# SparkFun_u-blox_SAM-M10Q.net
KiCad netlist of a schematic drawn in EAGLE
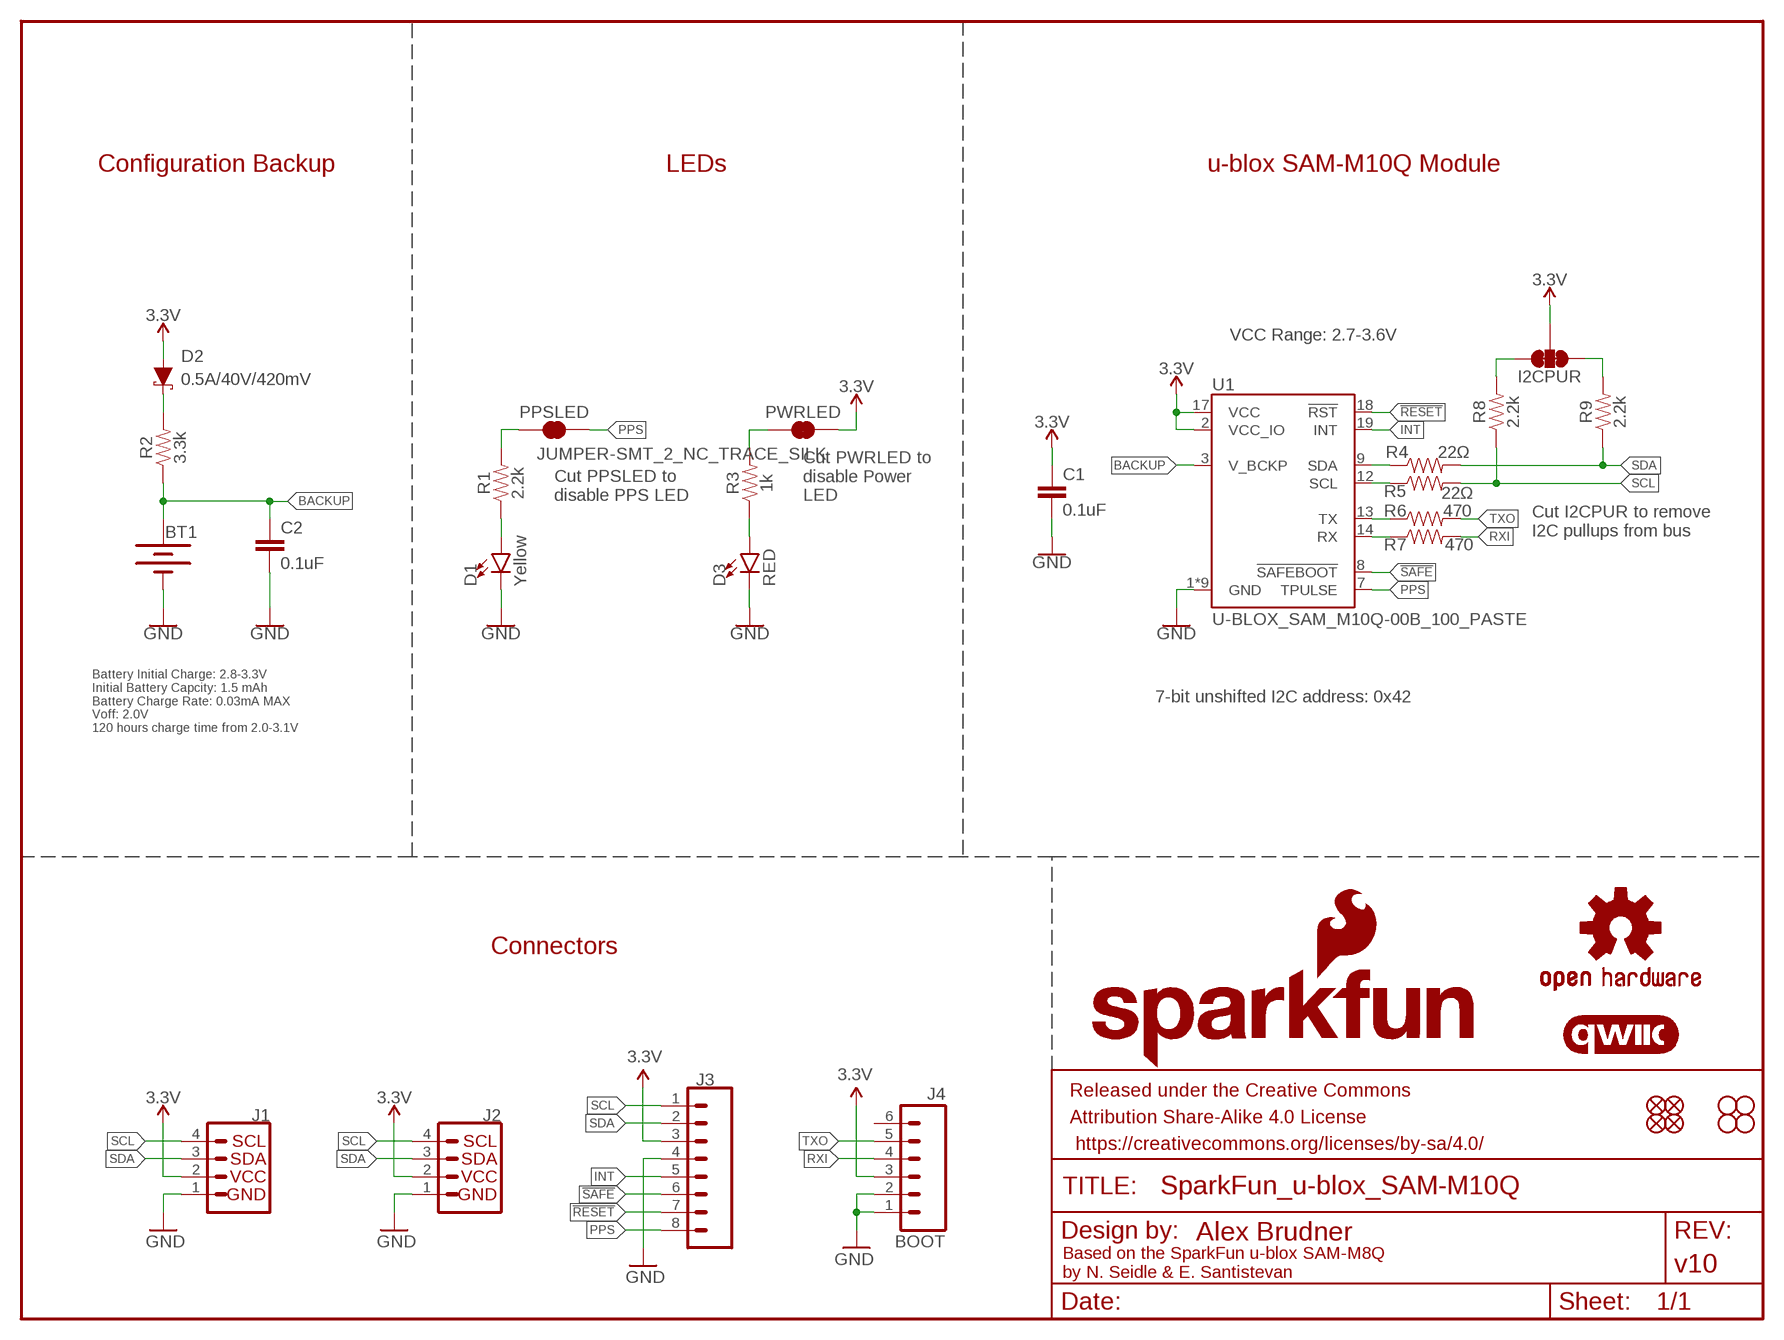
[diagram p0: schematic, sheet 1]

(export (version "E")
  (design (tool "Eeschema 10.0.6"))
  (components
    (comp (ref "BT1")
      (value "6.8MM_COIN_CELL")
      (footprint "eagle-import:MS421R_IV03E")
      (libsource (lib "eagle-import") (part "RELOWABLE_BATTERY_MS421R"))
    )
    (comp (ref "C1")
      (value "0.1uF")
      (footprint "eagle-import:0603")
      (libsource (lib "eagle-import") (part "0.1UF-0603-25V-(+80/-20%)"))
    )
    (comp (ref "C2")
      (value "0.1uF")
      (footprint "eagle-import:0603")
      (libsource (lib "eagle-import") (part "0.1UF-0603-25V-(+80/-20%)"))
    )
    (comp (ref "D1")
      (value "Yellow")
      (footprint "eagle-import:LED-0603")
      (libsource (lib "eagle-import") (part "LED-YELLOW0603"))
    )
    (comp (ref "D2")
      (value "0.5A/40V/420mV")
      (footprint "eagle-import:SOD-323")
      (libsource (lib "eagle-import") (part "DIODE-SCHOTTKY-PMEG4005EJ"))
    )
    (comp (ref "D3")
      (value "RED")
      (footprint "eagle-import:LED-0603")
      (libsource (lib "eagle-import") (part "LED-RED0603"))
    )
    (comp (ref "FD1")
      (value "FIDUCIALUFIDUCIAL")
      (footprint "eagle-import:FIDUCIAL-MICRO")
      (libsource (lib "eagle-import") (part "FIDUCIALUFIDUCIAL"))
    )
    (comp (ref "FD2")
      (value "FIDUCIALUFIDUCIAL")
      (footprint "eagle-import:FIDUCIAL-MICRO")
      (libsource (lib "eagle-import") (part "FIDUCIALUFIDUCIAL"))
    )
    (comp (ref "FD3")
      (value "FIDUCIALUFIDUCIAL")
      (footprint "eagle-import:FIDUCIAL-MICRO")
      (libsource (lib "eagle-import") (part "FIDUCIALUFIDUCIAL"))
    )
    (comp (ref "FD4")
      (value "FIDUCIALUFIDUCIAL")
      (footprint "eagle-import:FIDUCIAL-MICRO")
      (libsource (lib "eagle-import") (part "FIDUCIALUFIDUCIAL"))
    )
    (comp (ref "FRAME1")
      (value "FRAME-LETTER")
      (footprint "eagle-import:CREATIVE_COMMONS")
      (fields (field (name "DESIGNER") "Alex Brudner") (field (name "REV") "v10"))
      (libsource (lib "eagle-import") (part "FRAME-LETTER"))
    )
    (comp (ref "H1")
      (value "STAND-OFF")
      (footprint "eagle-import:STAND-OFF")
      (libsource (lib "eagle-import") (part "STAND-OFF"))
    )
    (comp (ref "H2")
      (value "STAND-OFF")
      (footprint "eagle-import:STAND-OFF")
      (libsource (lib "eagle-import") (part "STAND-OFF"))
    )
    (comp (ref "H3")
      (value "STAND-OFF")
      (footprint "eagle-import:STAND-OFF")
      (libsource (lib "eagle-import") (part "STAND-OFF"))
    )
    (comp (ref "H4")
      (value "STAND-OFF")
      (footprint "eagle-import:STAND-OFF")
      (libsource (lib "eagle-import") (part "STAND-OFF"))
    )
    (comp (ref "I2CPUR")
      (value "JUMPER-SMT_3_2-NC_TRACE_SILK")
      (footprint "eagle-import:SMT-JUMPER_3_2-NC_TRACE_SILK")
      (libsource (lib "eagle-import") (part "JUMPER-SMT_3_2-NC_TRACE_SILK"))
    )
    (comp (ref "J1")
      (value "Qwiic Right Angle")
      (footprint "eagle-import:JST04_1MM_RA")
      (libsource (lib "eagle-import") (part "I2C_STANDARDQWIIC"))
    )
    (comp (ref "J2")
      (value "Qwiic Right Angle")
      (footprint "eagle-import:JST04_1MM_RA")
      (libsource (lib "eagle-import") (part "I2C_STANDARDQWIIC"))
    )
    (comp (ref "J3")
      (value "CONN_08NO_SILK_FEMALE_PTH")
      (footprint "eagle-import:1X08_NO_SILK")
      (libsource (lib "eagle-import") (part "CONN_08NO_SILK_FEMALE_PTH"))
    )
    (comp (ref "J4")
      (value "BOOT")
      (footprint "eagle-import:1X06_NO_SILK")
      (libsource (lib "eagle-import") (part "CONN_06NO_SILK_NO_POP"))
    )
    (comp (ref "LOGO1")
      (value "OSHW-LOGOM")
      (footprint "eagle-import:OSHW-LOGO-M")
      (libsource (lib "eagle-import") (part "OSHW-LOGOM"))
    )
    (comp (ref "LOGO2")
      (value "SFE_LOGO_NAME_FLAME.2_INCH")
      (footprint "eagle-import:SFE_LOGO_NAME_FLAME_.2")
      (libsource (lib "eagle-import") (part "SFE_LOGO_NAME_FLAME.2_INCH"))
    )
    (comp (ref "LOGO3")
      (value "QWIIC_LOGO_CONNECTOR")
      (footprint "eagle-import:QWIIC_5.5MM")
      (libsource (lib "eagle-import") (part "QWIIC_LOGO_CONNECTOR"))
    )
    (comp (ref "PPSLED")
      (value "JUMPER-SMT_2_NC_TRACE_SILK")
      (footprint "eagle-import:SMT-JUMPER_2_NC_TRACE_SILK")
      (libsource (lib "eagle-import") (part "JUMPER-SMT_2_NC_TRACE_SILK"))
    )
    (comp (ref "PWRLED")
      (value "JUMPER-SMT_2_NC_TRACE_SILK")
      (footprint "eagle-import:SMT-JUMPER_2_NC_TRACE_SILK")
      (libsource (lib "eagle-import") (part "JUMPER-SMT_2_NC_TRACE_SILK"))
    )
    (comp (ref "R1")
      (value "2.2k")
      (footprint "eagle-import:0603")
      (libsource (lib "eagle-import") (part "2.2KOHM-0603-1/10W-1%"))
    )
    (comp (ref "R2")
      (value "3.3k")
      (footprint "eagle-import:0603")
      (libsource (lib "eagle-import") (part "3.3KOHM-0603-1/10W-1%"))
    )
    (comp (ref "R3")
      (value "1k")
      (footprint "eagle-import:0603")
      (libsource (lib "eagle-import") (part "1KOHM-0603-1/10W-1%"))
    )
    (comp (ref "R4")
      (value "22Ω")
      (footprint "eagle-import:0603")
      (libsource (lib "eagle-import") (part "22OHM-0603-1/10W-1%"))
    )
    (comp (ref "R5")
      (value "22Ω")
      (footprint "eagle-import:0603")
      (libsource (lib "eagle-import") (part "22OHM-0603-1/10W-1%"))
    )
    (comp (ref "R6")
      (value "470")
      (footprint "eagle-import:0603")
      (libsource (lib "eagle-import") (part "470OHM-0603-1/10W-1%"))
    )
    (comp (ref "R7")
      (value "470")
      (footprint "eagle-import:0603")
      (libsource (lib "eagle-import") (part "470OHM-0603-1/10W-1%"))
    )
    (comp (ref "R8")
      (value "2.2k")
      (footprint "eagle-import:0603")
      (libsource (lib "eagle-import") (part "2.2KOHM-0603-1/10W-1%"))
    )
    (comp (ref "R9")
      (value "2.2k")
      (footprint "eagle-import:0603")
      (libsource (lib "eagle-import") (part "2.2KOHM-0603-1/10W-1%"))
    )
    (comp (ref "U1")
      (value "U-BLOX_SAM_M10Q-00B_100_PASTE")
      (footprint "eagle-import:SAM-M10Q_100PASTE")
      (libsource (lib "eagle-import") (part "U-BLOX_SAM_M10Q-00B_100_PASTE"))
    )
  )
  (nets
    (net (code "1") (name "/~{RESET}") (class "Default")
      (node (ref "J3") (pin "7") (pinfunction "7_7") (pintype "passive"))
      (node (ref "U1") (pin "18") (pinfunction "~{RST}_18") (pintype "bidirectional"))
    )
    (net (code "2") (name "/~{SAFE}") (class "Default")
      (node (ref "J3") (pin "6") (pinfunction "6_6") (pintype "passive"))
      (node (ref "U1") (pin "8") (pinfunction "~{SAFEBOOT}_8") (pintype "bidirectional"))
    )
    (net (code "3") (name "3.3V") (class "Default")
      (node (ref "C1") (pin "1") (pinfunction "1_1") (pintype "passive"))
      (node (ref "D2") (pin "A") (pinfunction "A_A") (pintype "passive"))
      (node (ref "I2CPUR") (pin "2") (pinfunction "2_2") (pintype "passive"))
      (node (ref "J1") (pin "2") (pinfunction "2_2") (pintype "power_in"))
      (node (ref "J2") (pin "2") (pinfunction "2_2") (pintype "power_in"))
      (node (ref "J3") (pin "3") (pinfunction "3_3") (pintype "passive"))
      (node (ref "J4") (pin "3") (pinfunction "3_3") (pintype "passive"))
      (node (ref "PWRLED") (pin "2") (pinfunction "2_2") (pintype "passive"))
      (node (ref "U1") (pin "17") (pinfunction "VCC_17") (pintype "bidirectional"))
      (node (ref "U1") (pin "2") (pinfunction "VCC_IO_2") (pintype "bidirectional"))
    )
    (net (code "4") (name "BACKUP") (class "Default")
      (node (ref "BT1") (pin "+") (pinfunction "+_+") (pintype "power_in"))
      (node (ref "C2") (pin "1") (pinfunction "1_1") (pintype "passive"))
      (node (ref "R2") (pin "1") (pinfunction "1_1") (pintype "passive"))
      (node (ref "U1") (pin "3") (pinfunction "V_BCKP_3") (pintype "bidirectional"))
    )
    (net (code "5") (name "GND") (class "Default")
      (node (ref "BT1") (pin "-") (pinfunction "-_-") (pintype "power_in"))
      (node (ref "C1") (pin "2") (pinfunction "2_2") (pintype "passive"))
      (node (ref "C2") (pin "2") (pinfunction "2_2") (pintype "passive"))
      (node (ref "D1") (pin "C") (pinfunction "C_C") (pintype "passive"))
      (node (ref "D3") (pin "C") (pinfunction "C_C") (pintype "passive"))
      (node (ref "J1") (pin "1") (pinfunction "1_1") (pintype "power_in"))
      (node (ref "J2") (pin "1") (pinfunction "1_1") (pintype "power_in"))
      (node (ref "J3") (pin "4") (pinfunction "4_4") (pintype "passive"))
      (node (ref "J4") (pin "1") (pinfunction "1_1") (pintype "passive"))
      (node (ref "J4") (pin "2") (pinfunction "2_2") (pintype "passive"))
      (node (ref "U1") (pin "1") (pinfunction "GND_1") (pintype "bidirectional"))
      (node (ref "U1") (pin "10") (pinfunction "GND_10") (pintype "bidirectional"))
      (node (ref "U1") (pin "11") (pinfunction "GND_11") (pintype "bidirectional"))
      (node (ref "U1") (pin "15") (pinfunction "GND_15") (pintype "bidirectional"))
      (node (ref "U1") (pin "16") (pinfunction "GND_16") (pintype "bidirectional"))
      (node (ref "U1") (pin "20") (pinfunction "GND_20") (pintype "bidirectional"))
      (node (ref "U1") (pin "4") (pinfunction "GND_4") (pintype "bidirectional"))
      (node (ref "U1") (pin "5") (pinfunction "GND_5") (pintype "bidirectional"))
      (node (ref "U1") (pin "6") (pinfunction "GND_6") (pintype "bidirectional"))
    )
    (net (code "6") (name "INT") (class "Default")
      (node (ref "J3") (pin "5") (pinfunction "5_5") (pintype "passive"))
      (node (ref "U1") (pin "19") (pinfunction "INT_19") (pintype "bidirectional"))
    )
    (net (code "7") (name "Net-(D1-PadA)") (class "Default")
      (node (ref "D1") (pin "A") (pinfunction "A_A") (pintype "passive"))
      (node (ref "R1") (pin "1") (pinfunction "1_1") (pintype "passive"))
    )
    (net (code "8") (name "Net-(D2-PadC)") (class "Default")
      (node (ref "D2") (pin "C") (pinfunction "C_C") (pintype "passive"))
      (node (ref "R2") (pin "2") (pinfunction "2_2") (pintype "passive"))
    )
    (net (code "9") (name "Net-(D3-PadA)") (class "Default")
      (node (ref "D3") (pin "A") (pinfunction "A_A") (pintype "passive"))
      (node (ref "R3") (pin "1") (pinfunction "1_1") (pintype "passive"))
    )
    (net (code "10") (name "Net-(I2CPUR-Pad1)") (class "Default")
      (node (ref "I2CPUR") (pin "1") (pinfunction "1_1") (pintype "passive"))
      (node (ref "R9") (pin "2") (pinfunction "2_2") (pintype "passive"))
    )
    (net (code "11") (name "Net-(I2CPUR-Pad3)") (class "Default")
      (node (ref "I2CPUR") (pin "3") (pinfunction "3_3") (pintype "passive"))
      (node (ref "R8") (pin "2") (pinfunction "2_2") (pintype "passive"))
    )
    (net (code "12") (name "Net-(PPSLED-Pad1)") (class "Default")
      (node (ref "PPSLED") (pin "1") (pinfunction "1_1") (pintype "passive"))
      (node (ref "R1") (pin "2") (pinfunction "2_2") (pintype "passive"))
    )
    (net (code "13") (name "Net-(PWRLED-Pad1)") (class "Default")
      (node (ref "PWRLED") (pin "1") (pinfunction "1_1") (pintype "passive"))
      (node (ref "R3") (pin "2") (pinfunction "2_2") (pintype "passive"))
    )
    (net (code "14") (name "Net-(U1-RX)") (class "Default")
      (node (ref "R7") (pin "1") (pinfunction "1_1") (pintype "passive"))
      (node (ref "U1") (pin "14") (pinfunction "RX_14") (pintype "bidirectional"))
    )
    (net (code "15") (name "Net-(U1-SCL)") (class "Default")
      (node (ref "R5") (pin "1") (pinfunction "1_1") (pintype "passive"))
      (node (ref "U1") (pin "12") (pinfunction "SCL_12") (pintype "bidirectional"))
    )
    (net (code "16") (name "Net-(U1-SDA)") (class "Default")
      (node (ref "R4") (pin "1") (pinfunction "1_1") (pintype "passive"))
      (node (ref "U1") (pin "9") (pinfunction "SDA_9") (pintype "bidirectional"))
    )
    (net (code "17") (name "Net-(U1-TX)") (class "Default")
      (node (ref "R6") (pin "1") (pinfunction "1_1") (pintype "passive"))
      (node (ref "U1") (pin "13") (pinfunction "TX_13") (pintype "bidirectional"))
    )
    (net (code "18") (name "PPS") (class "Default")
      (node (ref "J3") (pin "8") (pinfunction "8_8") (pintype "passive"))
      (node (ref "PPSLED") (pin "2") (pinfunction "2_2") (pintype "passive"))
      (node (ref "U1") (pin "7") (pinfunction "TPULSE_7") (pintype "bidirectional"))
    )
    (net (code "19") (name "RXI") (class "Default")
      (node (ref "J4") (pin "4") (pinfunction "4_4") (pintype "passive"))
      (node (ref "R7") (pin "2") (pinfunction "2_2") (pintype "passive"))
    )
    (net (code "20") (name "SCL") (class "Default")
      (node (ref "J1") (pin "4") (pinfunction "4_4") (pintype "passive"))
      (node (ref "J2") (pin "4") (pinfunction "4_4") (pintype "passive"))
      (node (ref "J3") (pin "1") (pinfunction "1_1") (pintype "passive"))
      (node (ref "R5") (pin "2") (pinfunction "2_2") (pintype "passive"))
      (node (ref "R8") (pin "1") (pinfunction "1_1") (pintype "passive"))
    )
    (net (code "21") (name "SDA") (class "Default")
      (node (ref "J1") (pin "3") (pinfunction "3_3") (pintype "passive"))
      (node (ref "J2") (pin "3") (pinfunction "3_3") (pintype "passive"))
      (node (ref "J3") (pin "2") (pinfunction "2_2") (pintype "passive"))
      (node (ref "R4") (pin "2") (pinfunction "2_2") (pintype "passive"))
      (node (ref "R9") (pin "1") (pinfunction "1_1") (pintype "passive"))
    )
    (net (code "22") (name "TXO") (class "Default")
      (node (ref "J4") (pin "5") (pinfunction "5_5") (pintype "passive"))
      (node (ref "R6") (pin "2") (pinfunction "2_2") (pintype "passive"))
    )
    (net (code "23") (name "unconnected-(J4-Pad6)") (class "Default")
      (node (ref "J4") (pin "6") (pinfunction "6_6") (pintype "passive"))
    )
  )
)
